# 02_CONNECTION.net
KiCad netlist of a schematic drawn in Altium Designer
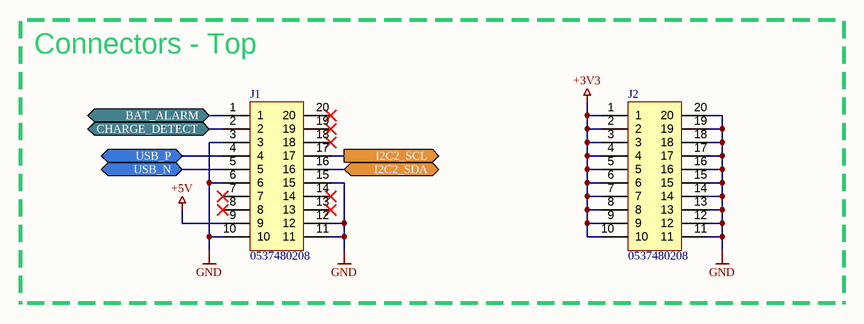
[diagram p0: 02 CONNECTION.SchDoc]

(export (version "E")
  (design (tool "Eeschema 10.0.6"))
  (components
    (comp (ref "J1")
      (value "0537480208")
      (footprint "0537480208")
      (description "CONN PLUG 20POS SMD GOLD")
      (fields (field (name "MANUFACTURER") "MOLEX"))
      (libsource (lib "altium_symbol") (part "0537480208"))
    )
    (comp (ref "J2")
      (value "0537480208")
      (footprint "0537480208")
      (description "CONN PLUG 20POS SMD GOLD")
      (fields (field (name "MANUFACTURER") "MOLEX"))
      (libsource (lib "altium_symbol") (part "0537480208"))
    )
  )
  (nets
    (net (code "1") (name "+3V3") (class "Default")
      (node (ref "J2") (pin "1") (pinfunction "1_1") (pintype "passive"))
      (node (ref "J2") (pin "10") (pinfunction "10_10") (pintype "passive"))
      (node (ref "J2") (pin "2") (pinfunction "2_2") (pintype "passive"))
      (node (ref "J2") (pin "3") (pinfunction "3_3") (pintype "passive"))
      (node (ref "J2") (pin "4") (pinfunction "4_4") (pintype "passive"))
      (node (ref "J2") (pin "5") (pinfunction "5_5") (pintype "passive"))
      (node (ref "J2") (pin "6") (pinfunction "6_6") (pintype "passive"))
      (node (ref "J2") (pin "7") (pinfunction "7_7") (pintype "passive"))
      (node (ref "J2") (pin "8") (pinfunction "8_8") (pintype "passive"))
      (node (ref "J2") (pin "9") (pinfunction "9_9") (pintype "passive"))
    )
    (net (code "2") (name "+5V") (class "Default")
      (node (ref "J1") (pin "9") (pinfunction "9_9") (pintype "passive"))
    )
    (net (code "3") (name "/BAT_ALARM") (class "Default")
      (node (ref "J1") (pin "1") (pinfunction "1_1") (pintype "passive"))
    )
    (net (code "4") (name "/CHARGE_DETECT") (class "Default")
      (node (ref "J1") (pin "2") (pinfunction "2_2") (pintype "passive"))
    )
    (net (code "5") (name "/I2C2_SCL") (class "Default")
      (node (ref "J1") (pin "17") (pinfunction "17_17") (pintype "passive"))
    )
    (net (code "6") (name "/I2C2_SDA") (class "Default")
      (node (ref "J1") (pin "16") (pinfunction "16_16") (pintype "passive"))
    )
    (net (code "7") (name "/USB_N") (class "Default")
      (node (ref "J1") (pin "5") (pinfunction "5_5") (pintype "passive"))
    )
    (net (code "8") (name "/USB_P") (class "Default")
      (node (ref "J1") (pin "4") (pinfunction "4_4") (pintype "passive"))
    )
    (net (code "9") (name "GND") (class "Default")
      (node (ref "J1") (pin "10") (pinfunction "10_10") (pintype "passive"))
      (node (ref "J1") (pin "11") (pinfunction "11_11") (pintype "passive"))
      (node (ref "J1") (pin "12") (pinfunction "12_12") (pintype "passive"))
      (node (ref "J1") (pin "15") (pinfunction "15_15") (pintype "passive"))
      (node (ref "J1") (pin "3") (pinfunction "3_3") (pintype "passive"))
      (node (ref "J1") (pin "6") (pinfunction "6_6") (pintype "passive"))
      (node (ref "J2") (pin "11") (pinfunction "11_11") (pintype "passive"))
      (node (ref "J2") (pin "12") (pinfunction "12_12") (pintype "passive"))
      (node (ref "J2") (pin "13") (pinfunction "13_13") (pintype "passive"))
      (node (ref "J2") (pin "14") (pinfunction "14_14") (pintype "passive"))
      (node (ref "J2") (pin "15") (pinfunction "15_15") (pintype "passive"))
      (node (ref "J2") (pin "16") (pinfunction "16_16") (pintype "passive"))
      (node (ref "J2") (pin "17") (pinfunction "17_17") (pintype "passive"))
      (node (ref "J2") (pin "18") (pinfunction "18_18") (pintype "passive"))
      (node (ref "J2") (pin "19") (pinfunction "19_19") (pintype "passive"))
      (node (ref "J2") (pin "20") (pinfunction "20_20") (pintype "passive"))
    )
    (net (code "10") (name "unconnected-(J1-Pad7)") (class "Default")
      (node (ref "J1") (pin "7") (pinfunction "7_7") (pintype "passive+no_connect"))
    )
    (net (code "11") (name "unconnected-(J1-Pad8)") (class "Default")
      (node (ref "J1") (pin "8") (pinfunction "8_8") (pintype "passive+no_connect"))
    )
    (net (code "12") (name "unconnected-(J1-Pad13)") (class "Default")
      (node (ref "J1") (pin "13") (pinfunction "13_13") (pintype "passive+no_connect"))
    )
    (net (code "13") (name "unconnected-(J1-Pad14)") (class "Default")
      (node (ref "J1") (pin "14") (pinfunction "14_14") (pintype "passive+no_connect"))
    )
    (net (code "14") (name "unconnected-(J1-Pad18)") (class "Default")
      (node (ref "J1") (pin "18") (pinfunction "18_18") (pintype "passive+no_connect"))
    )
    (net (code "15") (name "unconnected-(J1-Pad19)") (class "Default")
      (node (ref "J1") (pin "19") (pinfunction "19_19") (pintype "passive+no_connect"))
    )
    (net (code "16") (name "unconnected-(J1-Pad20)") (class "Default")
      (node (ref "J1") (pin "20") (pinfunction "20_20") (pintype "passive+no_connect"))
    )
  )
)
